# Amplifier_For_Term.net
KiCad netlist of a schematic drawn in Altium Designer
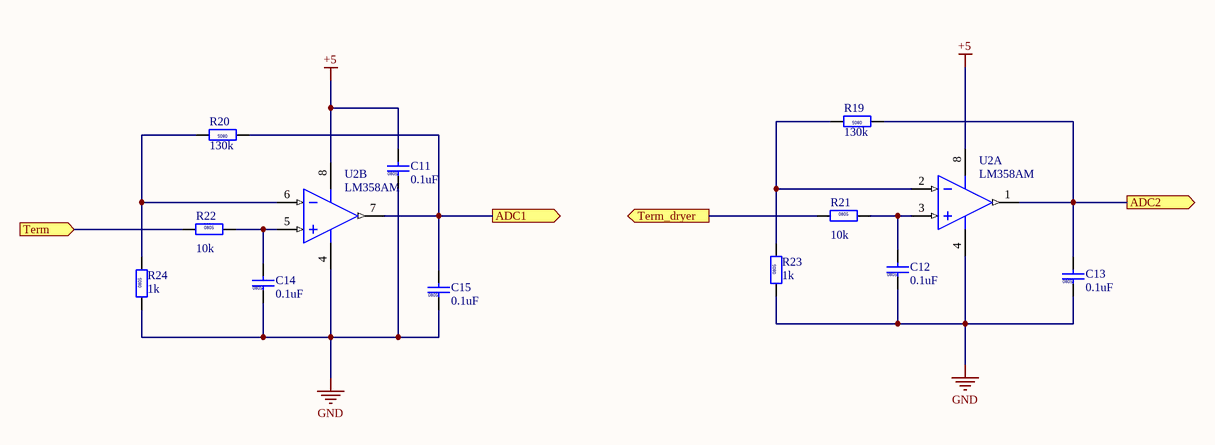
[diagram p0: Amplifier_For_Term.SchDoc]

(export (version "E")
  (design (tool "Eeschema 10.0.6"))
  (components
    (comp (ref "C11")
      (value "0.1uF")
      (footprint "CAPC2012-0805M")
      (description "Capacitor 0805")
      (fields (field (name "Comment") "CAPC_0805"))
      (libsource (lib "Passive") (part "CAPC_0805"))
    )
    (comp (ref "C12")
      (value "0.1uF")
      (footprint "CAPC2012-0805M")
      (description "Capacitor 0805")
      (fields (field (name "Comment") "CAPC_0805"))
      (libsource (lib "Passive") (part "CAPC_0805"))
    )
    (comp (ref "C13")
      (value "0.1uF")
      (footprint "CAPC2012-0805M")
      (description "Capacitor 0805")
      (fields (field (name "Comment") "CAPC_0805"))
      (libsource (lib "Passive") (part "CAPC_0805"))
    )
    (comp (ref "C14")
      (value "0.1uF")
      (footprint "CAPC2012-0805M")
      (description "Capacitor 0805")
      (fields (field (name "Comment") "CAPC_0805"))
      (libsource (lib "Passive") (part "CAPC_0805"))
    )
    (comp (ref "C15")
      (value "0.1uF")
      (footprint "CAPC2012-0805M")
      (description "Capacitor 0805")
      (fields (field (name "Comment") "CAPC_0805"))
      (libsource (lib "Passive") (part "CAPC_0805"))
    )
    (comp (ref "R19")
      (value "130k")
      (footprint "RESC2012-0805M")
      (description "Resistor 0805")
      (fields (field (name "Comment") "RESC_0805_R"))
      (libsource (lib "") (part "RESC_0805_R_1"))
    )
    (comp (ref "R20")
      (value "130k")
      (footprint "RESC2012-0805M")
      (description "Resistor 0805")
      (fields (field (name "Comment") "RESC_0805_R"))
      (libsource (lib "") (part "RESC_0805_R_1"))
    )
    (comp (ref "R21")
      (value "10k")
      (footprint "RESC2012-0805M")
      (description "Resistor 0805")
      (fields (field (name "Comment") "RESC_0805_R"))
      (libsource (lib "") (part "RESC_0805_R_2"))
    )
    (comp (ref "R22")
      (value "10k")
      (footprint "RESC2012-0805M")
      (description "Resistor 0805")
      (fields (field (name "Comment") "RESC_0805_R"))
      (libsource (lib "") (part "RESC_0805_R_2"))
    )
    (comp (ref "R23")
      (value "1k")
      (footprint "RESC2012-0805M")
      (description "Resistor 0805")
      (fields (field (name "Comment") "RESC_0805_R"))
      (libsource (lib "Passive") (part "RESC_0805_R"))
    )
    (comp (ref "R24")
      (value "1k")
      (footprint "RESC2012-0805M")
      (description "Resistor 0805")
      (fields (field (name "Comment") "RESC_0805_R"))
      (libsource (lib "Passive") (part "RESC_0805_R"))
    )
    (comp (ref "U2")
      (value "LM358AM")
      (footprint "SO-8_L")
      (description "Low Power Dual Operational Amplifier")
      (fields
        (field (name "MANUFACTURER") "National Semiconductor")
        (field (name "DIGIKEYPARTNUMBER") "LM358AMXCT-ND")
        (field (name "PUBLISHER") "Altium Limited")
      )
      (libsource (lib "Analog_IC") (part "LM358AM"))
    )
  )
  (nets
    (net (code "1") (name "+5") (class "Default")
      (node (ref "C11") (pin "2") (pinfunction "2_2") (pintype "passive"))
      (node (ref "U2") (pin "8") (pinfunction "V+_8") (pintype "power_in"))
    )
    (net (code "2") (name "/ADC1") (class "Default")
      (node (ref "C15") (pin "2") (pinfunction "2_2") (pintype "passive"))
      (node (ref "R20") (pin "1") (pinfunction "1_1") (pintype "passive"))
      (node (ref "U2") (pin "7") (pinfunction "OUTB_7") (pintype "output"))
    )
    (net (code "3") (name "/ADC2") (class "Default")
      (node (ref "C13") (pin "2") (pinfunction "2_2") (pintype "passive"))
      (node (ref "R19") (pin "1") (pinfunction "1_1") (pintype "passive"))
      (node (ref "U2") (pin "1") (pinfunction "OUTA_1") (pintype "output"))
    )
    (net (code "4") (name "/Term") (class "Default")
      (node (ref "R22") (pin "1") (pinfunction "1_1") (pintype "passive"))
    )
    (net (code "5") (name "/Term_dryer") (class "Default")
      (node (ref "R21") (pin "1") (pinfunction "1_1") (pintype "passive"))
    )
    (net (code "6") (name "GND") (class "Default")
      (node (ref "C11") (pin "1") (pinfunction "1_1") (pintype "passive"))
      (node (ref "C12") (pin "1") (pinfunction "1_1") (pintype "passive"))
      (node (ref "C13") (pin "1") (pinfunction "1_1") (pintype "passive"))
      (node (ref "C14") (pin "1") (pinfunction "1_1") (pintype "passive"))
      (node (ref "C15") (pin "1") (pinfunction "1_1") (pintype "passive"))
      (node (ref "R23") (pin "1") (pinfunction "1_1") (pintype "passive"))
      (node (ref "R24") (pin "1") (pinfunction "1_1") (pintype "passive"))
      (node (ref "U2") (pin "4") (pinfunction "GND_4") (pintype "power_in"))
    )
    (net (code "7") (name "Net-(U2A-INA+)") (class "Default")
      (node (ref "C12") (pin "2") (pinfunction "2_2") (pintype "passive"))
      (node (ref "R21") (pin "2") (pinfunction "2_2") (pintype "passive"))
      (node (ref "U2") (pin "3") (pinfunction "INA+_3") (pintype "input"))
    )
    (net (code "8") (name "Net-(U2A-INA-)") (class "Default")
      (node (ref "R19") (pin "2") (pinfunction "2_2") (pintype "passive"))
      (node (ref "R23") (pin "2") (pinfunction "2_2") (pintype "passive"))
      (node (ref "U2") (pin "2") (pinfunction "INA-_2") (pintype "input"))
    )
    (net (code "9") (name "Net-(U2B-INB+)") (class "Default")
      (node (ref "C14") (pin "2") (pinfunction "2_2") (pintype "passive"))
      (node (ref "R22") (pin "2") (pinfunction "2_2") (pintype "passive"))
      (node (ref "U2") (pin "5") (pinfunction "INB+_5") (pintype "input"))
    )
    (net (code "10") (name "Net-(U2B-INB-)") (class "Default")
      (node (ref "R20") (pin "2") (pinfunction "2_2") (pintype "passive"))
      (node (ref "R24") (pin "2") (pinfunction "2_2") (pintype "passive"))
      (node (ref "U2") (pin "6") (pinfunction "INB-_6") (pintype "input"))
    )
  )
)
